# Mach_dieu_khien_tu_xa.net
KiCad netlist of a schematic drawn in Altium Designer
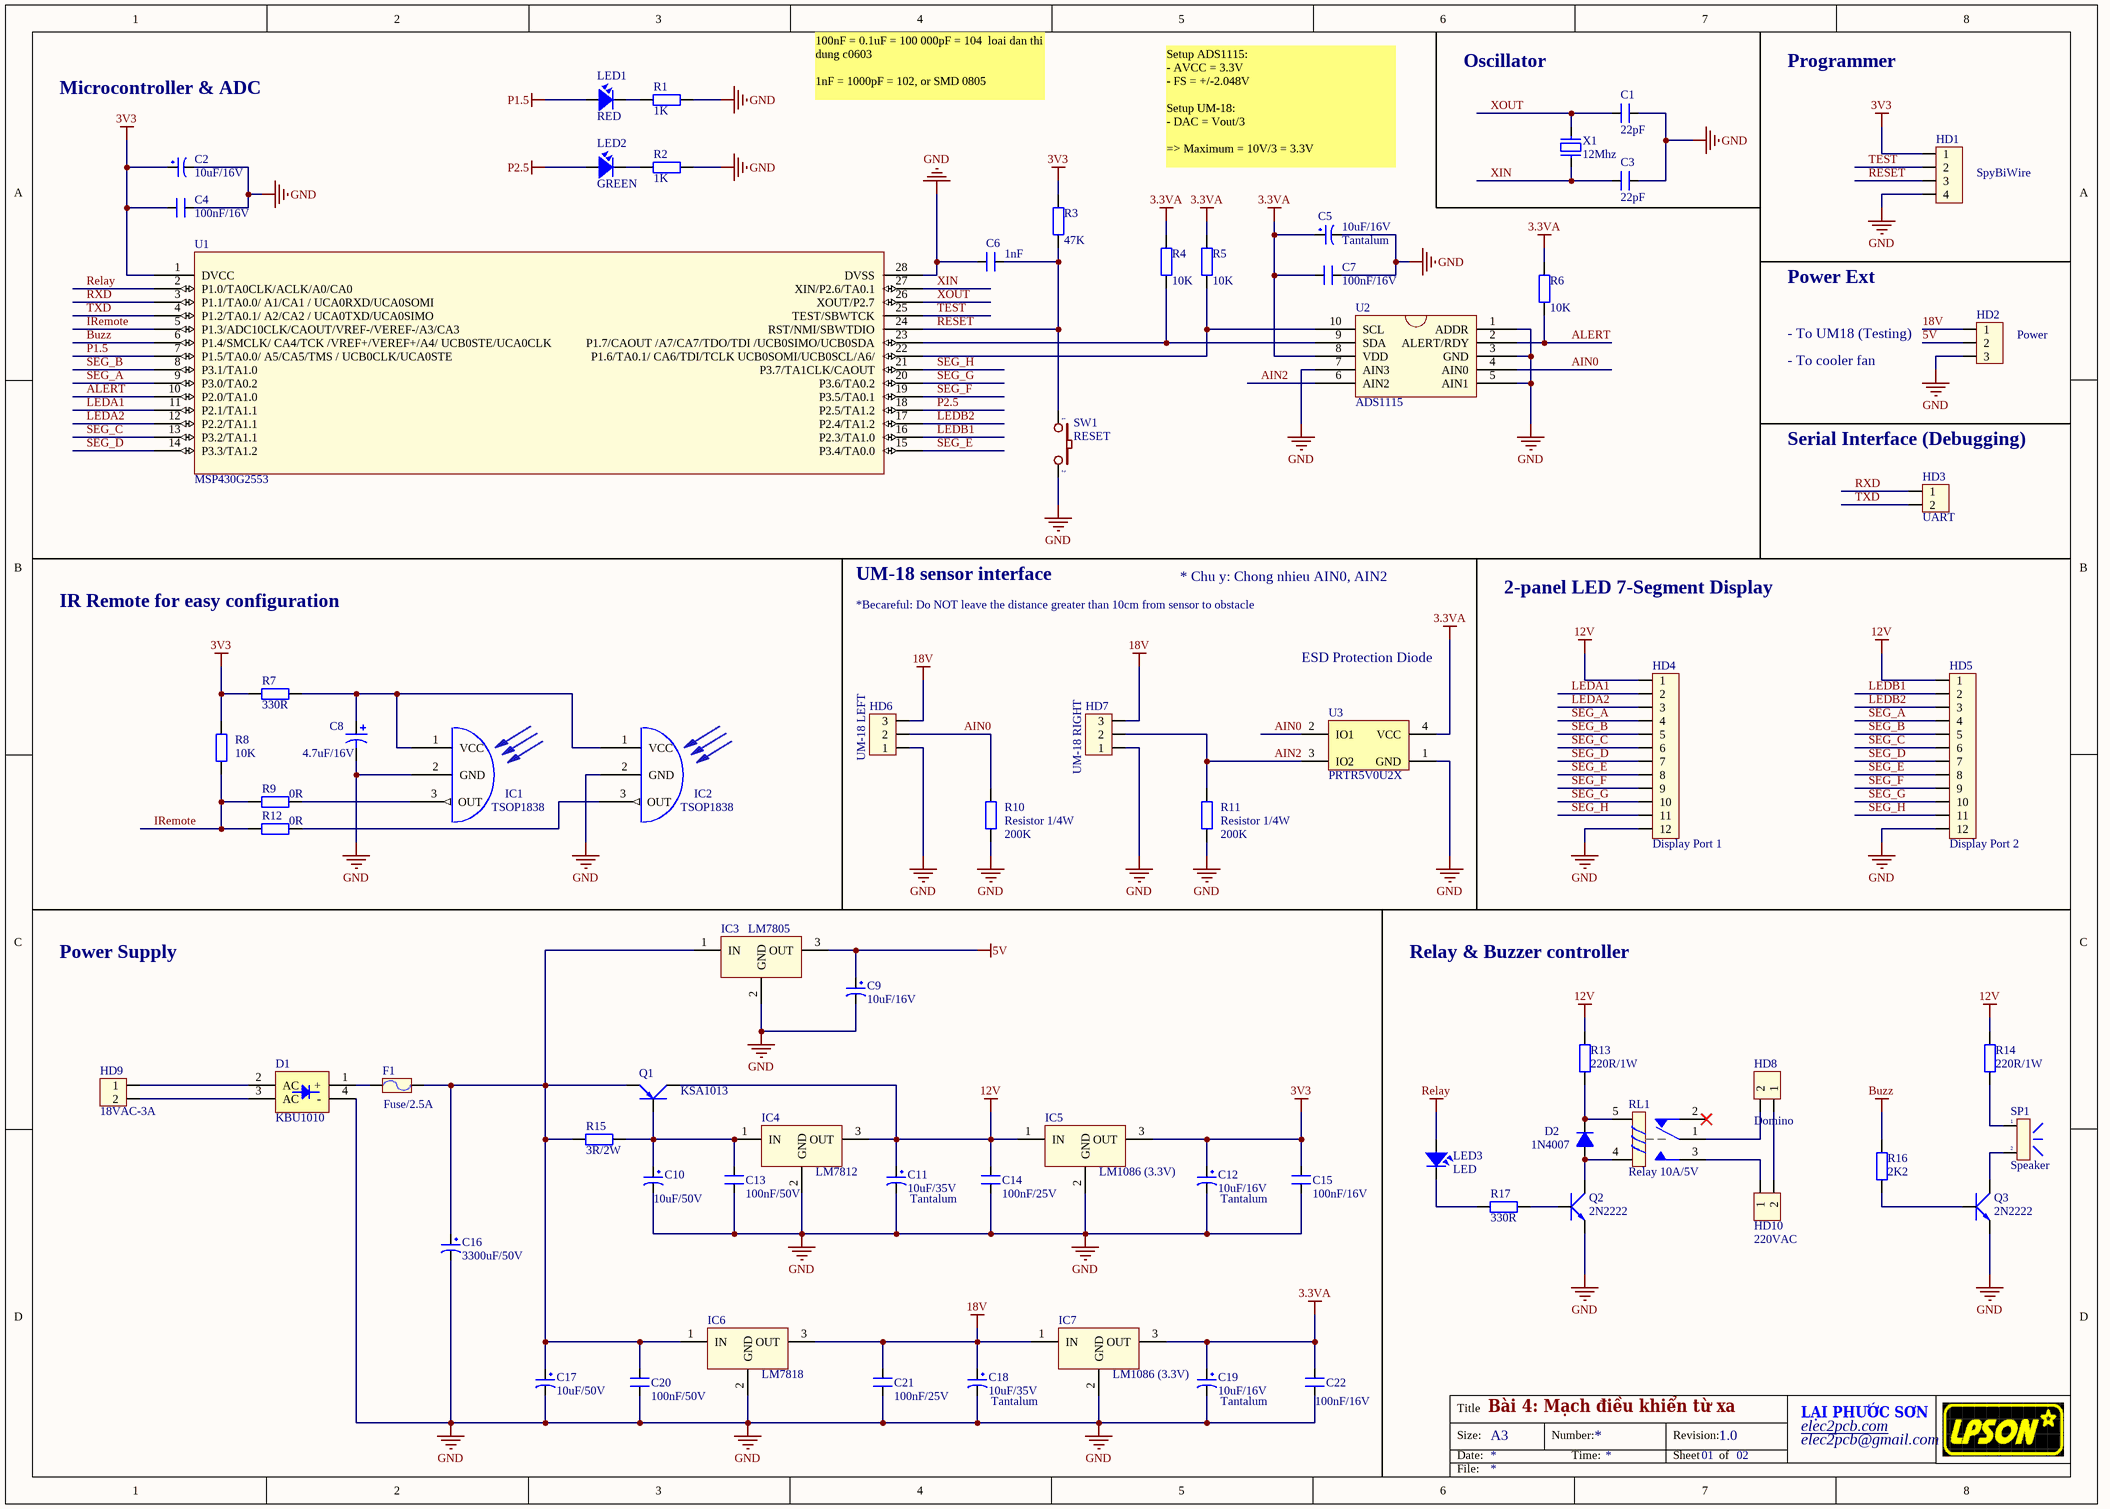
[diagram p0: Mach dieu khien tu xa.SchDoc]

(export (version "E")
  (design (tool "Eeschema 10.0.6"))
  (components
    (comp (ref "C1")
      (value "22pF")
      (footprint "C0603")
      (description "0805-SMD Capacitor")
      (libsource (lib "syhaunguyen") (part "CN1"))
    )
    (comp (ref "C2")
      (value "10uF/16V")
      (footprint "C0805")
      (description "Cap P  0,1uF < 22uF , 16 - 50V")
      (libsource (lib "") (part "CP1_1"))
    )
    (comp (ref "C3")
      (value "22pF")
      (footprint "C0603")
      (description "0805-SMD Capacitor")
      (libsource (lib "syhaunguyen") (part "CN1"))
    )
    (comp (ref "C4")
      (value "100nF/16V")
      (footprint "Tu gom 104")
      (description "Cap np 104 => 105pF")
      (libsource (lib "VNELEK") (part "CN2"))
    )
    (comp (ref "C5")
      (value "10uF/16V")
      (footprint "CAP_TANTA_10UF_16V")
      (description "Tantalum Capacitor")
      (fields (field (name "TYPE") "Tantalum"))
      (libsource (lib "") (part "CP1_1"))
    )
    (comp (ref "C6")
      (value "1nF")
      (footprint "C0805")
      (description "Cap np 104 => 105pF")
      (libsource (lib "VNELEK") (part "CN2"))
    )
    (comp (ref "C7")
      (value "100nF/16V")
      (footprint "Tu gom 104")
      (description "Cap np 104 => 105pF")
      (libsource (lib "VNELEK") (part "CN2"))
    )
    (comp (ref "C8")
      (value "4.7uF/16V")
      (footprint "C0805")
      (description "Polarized Capacitor (Radial)")
      (fields (field (name "Comment") "Cap Pol1") (field (name "PUBLISHER") "Altium Limited"))
      (libsource (lib "Miscellaneous Devices") (part "Cap Pol1"))
    )
    (comp (ref "C9")
      (value "10uF/16V")
      (footprint "CAP_10UF_16V")
      (description "Aluminium Capacitor")
      (libsource (lib "VNELEK") (part "CP1"))
    )
    (comp (ref "C10")
      (value "10uF/50V")
      (footprint "C_FC_10UF_50V")
      (description "Aluminium Capacitor")
      (libsource (lib "VNELEK") (part "CP1"))
    )
    (comp (ref "C11")
      (value "10uF/35V")
      (footprint "CAP_TANTA_10UF_35V")
      (description "Tantalum Capacitor")
      (fields (field (name "TYPE") "Tantalum"))
      (libsource (lib "VNELEK") (part "CP1"))
    )
    (comp (ref "C12")
      (value "10uF/16V")
      (footprint "CAP_TANTA_10UF_16V")
      (description "Tantalum Capacitor")
      (fields (field (name "TYPE") "Tantalum"))
      (libsource (lib "VNELEK") (part "CP1"))
    )
    (comp (ref "C13")
      (value "100nF/50V")
      (footprint "Tu gom 104")
      (description "Cap np 104 => 105pF")
      (libsource (lib "VNELEK") (part "CN2"))
    )
    (comp (ref "C14")
      (value "100nF/25V")
      (footprint "Tu gom 104")
      (description "Cap np 104 => 105pF")
      (libsource (lib "VNELEK") (part "CN2"))
    )
    (comp (ref "C15")
      (value "100nF/16V")
      (footprint "Tu gom 104")
      (description "Cap np 104 => 105pF")
      (libsource (lib "VNELEK") (part "CN2"))
    )
    (comp (ref "C16")
      (value "3300uF/50V")
      (footprint "CAP_3300UF_50V")
      (description "Cap P  0,1uF < 22uF , 16 - 50V")
      (libsource (lib "VNELEK") (part "CP1"))
    )
    (comp (ref "C17")
      (value "10uF/50V")
      (footprint "C_FC_10UF_50V")
      (description "Aluminium Capacitor")
      (libsource (lib "VNELEK") (part "CP1"))
    )
    (comp (ref "C18")
      (value "10uF/35V")
      (footprint "CAP_TANTA_10UF_35V")
      (description "Tantalum Capacitor")
      (fields (field (name "TYPE") "Tantalum"))
      (libsource (lib "VNELEK") (part "CP1"))
    )
    (comp (ref "C19")
      (value "10uF/16V")
      (footprint "CAP_TANTA_10UF_16V")
      (description "Tantalum Capacitor")
      (fields (field (name "TYPE") "Tantalum"))
      (libsource (lib "VNELEK") (part "CP1"))
    )
    (comp (ref "C20")
      (value "100nF/50V")
      (footprint "Tu gom 104")
      (description "Cap np 104 => 105pF")
      (libsource (lib "VNELEK") (part "CN2"))
    )
    (comp (ref "C21")
      (value "100nF/25V")
      (footprint "Tu gom 104")
      (description "Cap np 104 => 105pF")
      (libsource (lib "VNELEK") (part "CN2"))
    )
    (comp (ref "C22")
      (value "100nF/16V")
      (footprint "Tu gom 104")
      (description "Cap np 104 => 105pF")
      (libsource (lib "VNELEK") (part "CN2"))
    )
    (comp (ref "D1")
      (value "KBU1010")
      (footprint "KBU1010G")
      (description "10A glass passivated bridge rectifier")
      (libsource (lib "Tran Tuan") (part "KBU1010"))
    )
    (comp (ref "D2")
      (value "1N4007")
      (footprint "1N4007")
      (description "Diode 1A")
      (libsource (lib "VNELEK") (part "D1A"))
    )
    (comp (ref "F1")
      (value "Fuse/2.5A")
      (footprint "FUSE2_5A")
      (description "Fuse")
      (fields (field (name "DESIGNED BY") "VanDungEvn"))
      (libsource (lib "VNELEK") (part "Fuse"))
    )
    (comp (ref "HD1")
      (value "SpyBiWire")
      (footprint "Header_4")
      (description "Header 4 (Green)")
      (libsource (lib "VNELEK") (part "Hed4"))
    )
    (comp (ref "HD2")
      (value "Power")
      (footprint "CON3")
      (description "Header 3 (Green)")
      (libsource (lib "VNELEK") (part "Hed3"))
    )
    (comp (ref "HD3")
      (value "UART")
      (footprint "Header_2")
      (description "Header 2 (Green)")
      (libsource (lib "VNELEK") (part "Hed2"))
    )
    (comp (ref "HD4")
      (value "Display Port 1")
      (footprint "CON12")
      (description "Header 12")
      (libsource (lib "Tran Tuan") (part "Hed12"))
    )
    (comp (ref "HD5")
      (value "Display Port 2")
      (footprint "CON12")
      (description "Header 12")
      (libsource (lib "Tran Tuan") (part "Hed12"))
    )
    (comp (ref "HD6")
      (value "UM-18 LEFT")
      (footprint "CON3")
      (description "Header 3 (Green)")
      (libsource (lib "") (part "Hed3_1"))
    )
    (comp (ref "HD7")
      (value "UM-18 RIGHT")
      (footprint "CON3")
      (description "Header 3 (Green)")
      (libsource (lib "") (part "Hed3_1"))
    )
    (comp (ref "HD8")
      (value "Domino")
      (footprint "DOMINO2_GREEN")
      (description "Header 2 (Green)")
      (libsource (lib "VNELEK") (part "Hed2"))
    )
    (comp (ref "HD9")
      (value "18VAC-3A")
      (footprint "DOMINO2_GREEN")
      (description "Header 2 (Green)")
      (libsource (lib "") (part "Hed2_1"))
    )
    (comp (ref "HD10")
      (value "220VAC")
      (footprint "DOMINO2_GREEN")
      (description "Header 2 (Green)")
      (libsource (lib "") (part "Hed2_2"))
    )
    (comp (ref "IC1")
      (value "TSOP1838")
      (footprint "TSOP1838")
      (libsource (lib "Tran Tuan") (part "TSOP1838"))
    )
    (comp (ref "IC2")
      (value "TSOP1838")
      (footprint "TSOP1838")
      (libsource (lib "Tran Tuan") (part "TSOP1838"))
    )
    (comp (ref "IC3")
      (value "LM7805")
      (footprint "LM7805")
      (description "Linear Regulator")
      (libsource (lib "VNELEK") (part "LM78xx"))
    )
    (comp (ref "IC4")
      (value "LM7812")
      (footprint "LM7805")
      (description "Linear Regulator")
      (fields (field (name "MANUFACTURER") "Fairchild Semiconductor"))
      (libsource (lib "VNELEK") (part "LM78xx"))
    )
    (comp (ref "IC5")
      (value "LM1086 (3.3V)")
      (footprint "LM1086")
      (description "Linear Regulator")
      (libsource (lib "VNELEK") (part "LM78xx"))
    )
    (comp (ref "IC6")
      (value "LM7818")
      (footprint "LM7805")
      (description "Linear Regulator")
      (libsource (lib "VNELEK") (part "LM78xx"))
    )
    (comp (ref "IC7")
      (value "LM1086 (3.3V)")
      (footprint "LM1086")
      (description "Linear Regulator")
      (libsource (lib "VNELEK") (part "LM78xx"))
    )
    (comp (ref "LED1")
      (value "RED")
      (footprint "LED3R")
      (description "LED Single colour Green and Red")
      (libsource (lib "VNELEK") (part "LED"))
    )
    (comp (ref "LED2")
      (value "GREEN")
      (footprint "LED3R")
      (description "LED Single colour Green and Red")
      (libsource (lib "VNELEK") (part "LED"))
    )
    (comp (ref "LED3")
      (value "LED")
      (footprint "LED3R")
      (description "LED Single colour Green and Red")
      (libsource (lib "VNELEK") (part "LED"))
    )
    (comp (ref "Q1")
      (value "KSA1013")
      (footprint "KSA1013")
      (description "PNP 600mW, ECB")
      (fields (field (name "MANUFACTURER") "Fairchild Semiconductor"))
      (libsource (lib "VNELEK") (part "A1015"))
    )
    (comp (ref "Q2")
      (value "2N2222")
      (footprint "2N2222")
      (description "TRANS GP SS NPN LP 40V TO92")
      (libsource (lib "VNELEK") (part "C1815"))
    )
    (comp (ref "Q3")
      (value "2N2222")
      (footprint "2N2222")
      (description "TRANS GP SS NPN LP 40V TO92")
      (libsource (lib "VNELEK") (part "C1815"))
    )
    (comp (ref "R1")
      (value "1K")
      (footprint "RESC2012(0805)")
      (description "Resistor")
      (fields (field (name "Comment") "Res2") (field (name "PUBLISHER") "Altium Limited"))
      (libsource (lib "") (part "Res2_2"))
    )
    (comp (ref "R2")
      (value "1K")
      (footprint "RESC2012(0805)")
      (description "Resistor")
      (fields (field (name "Comment") "Res2") (field (name "PUBLISHER") "Altium Limited"))
      (libsource (lib "") (part "Res2_2"))
    )
    (comp (ref "R3")
      (value "47K")
      (footprint "RESC2012(0805)")
      (description "Resistor")
      (fields (field (name "Comment") "Res2") (field (name "PUBLISHER") "Altium Limited"))
      (libsource (lib "Miscellaneous Devices") (part "Res2"))
    )
    (comp (ref "R4")
      (value "10K")
      (footprint "RESC2012(0805)")
      (description "Resistor")
      (fields (field (name "Comment") "Res2") (field (name "PUBLISHER") "Altium Limited"))
      (libsource (lib "Miscellaneous Devices") (part "Res2"))
    )
    (comp (ref "R5")
      (value "10K")
      (footprint "RESC2012(0805)")
      (description "Resistor")
      (fields (field (name "Comment") "Res2") (field (name "PUBLISHER") "Altium Limited"))
      (libsource (lib "Miscellaneous Devices") (part "Res2"))
    )
    (comp (ref "R6")
      (value "10K")
      (footprint "RESC2012(0805)")
      (description "Resistor")
      (fields (field (name "Comment") "Res2") (field (name "PUBLISHER") "Altium Limited"))
      (libsource (lib "Miscellaneous Devices") (part "Res2"))
    )
    (comp (ref "R7")
      (value "330R")
      (footprint "RESC2012(0805)")
      (description "Resistor")
      (fields (field (name "Comment") "Res2") (field (name "PUBLISHER") "Altium Limited"))
      (libsource (lib "") (part "Res2_2"))
    )
    (comp (ref "R8")
      (value "10K")
      (footprint "RESC2012(0805)")
      (description "Resistor")
      (fields (field (name "Comment") "Res2") (field (name "PUBLISHER") "Altium Limited"))
      (libsource (lib "Miscellaneous Devices") (part "Res2"))
    )
    (comp (ref "R9")
      (value "0R")
      (footprint "RESC2012(0805)")
      (description "Resistor")
      (fields (field (name "Comment") "Res2") (field (name "PUBLISHER") "Altium Limited"))
      (libsource (lib "") (part "Res2_2"))
    )
    (comp (ref "R10")
      (value "Resistor 1/4W")
      (footprint "RESC2012(0805)")
      (fields (field (name "ALTIUM_VALUE") "200K"))
      (libsource (lib "") (part "Res2_1"))
    )
    (comp (ref "R11")
      (value "Resistor 1/4W")
      (footprint "RESC2012(0805)")
      (fields (field (name "ALTIUM_VALUE") "200K"))
      (libsource (lib "") (part "Res2_1"))
    )
    (comp (ref "R12")
      (value "0R")
      (footprint "RESC2012(0805)")
      (description "Resistor")
      (fields (field (name "Comment") "Res2") (field (name "PUBLISHER") "Altium Limited"))
      (libsource (lib "") (part "Res2_2"))
    )
    (comp (ref "R13")
      (value "220R/1W")
      (footprint "CFR1WS")
      (description "Resistor")
      (fields (field (name "Comment") "Res2") (field (name "PUBLISHER") "Altium Limited"))
      (libsource (lib "") (part "Res2_1"))
    )
    (comp (ref "R14")
      (value "220R/1W")
      (footprint "CFR1WS")
      (description "Resistor")
      (fields (field (name "Comment") "Res2") (field (name "PUBLISHER") "Altium Limited"))
      (libsource (lib "") (part "Res2_1"))
    )
    (comp (ref "R15")
      (value "3R/2W")
      (footprint "R2WD")
      (description "Resistor")
      (fields (field (name "Comment") "Res2") (field (name "PUBLISHER") "Altium Limited"))
      (libsource (lib "") (part "Res2_2"))
    )
    (comp (ref "R16")
      (value "2K2")
      (footprint "RES 1/4W CFR25")
      (description "Resistor")
      (fields (field (name "Comment") "Res2") (field (name "PUBLISHER") "Altium Limited"))
      (libsource (lib "") (part "Res2_1"))
    )
    (comp (ref "R17")
      (value "330R")
      (footprint "RES 1/4W CFR25")
      (description "Resistor")
      (fields (field (name "Comment") "Res2") (field (name "PUBLISHER") "Altium Limited"))
      (libsource (lib "") (part "Res2_2"))
    )
    (comp (ref "RL1")
      (value "Relay 10A/5V")
      (footprint "RL_10A_5V")
      (description "Relay SPDT,10A - 12VDC 5 Pin")
      (libsource (lib "VNELEK") (part "Relay 1"))
    )
    (comp (ref "SP1")
      (value "Speaker")
      (footprint "SPEAKER")
      (description "Speaker Chip")
      (libsource (lib "VNELEK") (part "SPK"))
    )
    (comp (ref "SW1")
      (value "RESET")
      (footprint "BUTTON 2PIN TRON")
      (description "Switch button 2 pin")
      (libsource (lib "VNELEK") (part "SW2"))
    )
    (comp (ref "U1")
      (value "MSP430G2553")
      (footprint "MSP430G2253IPW28R")
      (description "MSP430G2553 (28 pins)")
      (libsource (lib "Tran Tuan") (part "MSP430G2553"))
    )
    (comp (ref "U2")
      (value "ADS1115")
      (footprint "ADS1115")
      (description "Analog to Digital Converter")
      (libsource (lib "Tran Tuan") (part "ADS1115"))
    )
    (comp (ref "U3")
      (value "PRTR5V0U2X")
      (footprint "PRTR5V0U2X")
      (description "ESD protection diode")
      (libsource (lib "Tran Tuan") (part "PRTR5V0U2X"))
    )
    (comp (ref "X1")
      (value "12Mhz")
      (footprint "CRYSTAL")
      (description "Crystal For all Crystal 2pin.")
      (libsource (lib "syhaunguyen") (part "XT2"))
    )
  )
  (nets
    (net (code "1") (name "/AIN0") (class "Default")
      (node (ref "HD6") (pin "2") (pinfunction "2_2") (pintype "passive"))
      (node (ref "R10") (pin "1") (pinfunction "1_1") (pintype "passive"))
      (node (ref "U2") (pin "4") (pinfunction "AIN0_4") (pintype "passive"))
      (node (ref "U3") (pin "2") (pinfunction "IO1_2") (pintype "passive"))
    )
    (net (code "2") (name "/AIN2") (class "Default")
      (node (ref "HD7") (pin "2") (pinfunction "2_2") (pintype "passive"))
      (node (ref "R11") (pin "1") (pinfunction "1_1") (pintype "passive"))
      (node (ref "U2") (pin "6") (pinfunction "AIN2_6") (pintype "passive"))
      (node (ref "U3") (pin "3") (pinfunction "IO2_3") (pintype "passive"))
    )
    (net (code "3") (name "/ALERT") (class "Default")
      (node (ref "R6") (pin "1") (pinfunction "1_1") (pintype "passive"))
      (node (ref "U1") (pin "10") (pinfunction "P2.0/TA1.0_10") (pintype "bidirectional"))
      (node (ref "U2") (pin "2") (pinfunction "ALERT/RDY_2") (pintype "passive"))
    )
    (net (code "4") (name "/IRemote") (class "Default")
      (node (ref "R12") (pin "2") (pinfunction "2_2") (pintype "passive"))
      (node (ref "R8") (pin "1") (pinfunction "1_1") (pintype "passive"))
      (node (ref "R9") (pin "2") (pinfunction "2_2") (pintype "passive"))
      (node (ref "U1") (pin "5") (pinfunction "P1.3/ADC10CLK/CAOUT/VREF-/VEREF-/A3/CA3_5") (pintype "bidirectional"))
    )
    (net (code "5") (name "/LEDA1") (class "Default")
      (node (ref "HD4") (pin "2") (pinfunction "2_2") (pintype "passive"))
      (node (ref "U1") (pin "11") (pinfunction "P2.1/TA1.1_11") (pintype "bidirectional"))
    )
    (net (code "6") (name "/LEDA2") (class "Default")
      (node (ref "HD4") (pin "3") (pinfunction "3_3") (pintype "passive"))
      (node (ref "U1") (pin "12") (pinfunction "P2.2/TA1.1_12") (pintype "bidirectional"))
    )
    (net (code "7") (name "/LEDB1") (class "Default")
      (node (ref "HD5") (pin "2") (pinfunction "2_2") (pintype "passive"))
      (node (ref "U1") (pin "16") (pinfunction "P2.3/TA1.0_16") (pintype "bidirectional"))
    )
    (net (code "8") (name "/LEDB2") (class "Default")
      (node (ref "HD5") (pin "3") (pinfunction "3_3") (pintype "passive"))
      (node (ref "U1") (pin "17") (pinfunction "P2.4/TA1.2_17") (pintype "bidirectional"))
    )
    (net (code "9") (name "/RESET") (class "Default")
      (node (ref "C6") (pin "2") (pinfunction "2_2") (pintype "passive"))
      (node (ref "HD1") (pin "3") (pinfunction "3_3") (pintype "passive"))
      (node (ref "R3") (pin "1") (pinfunction "1_1") (pintype "passive"))
      (node (ref "SW1") (pin "1") (pinfunction "1_1") (pintype "passive"))
      (node (ref "U1") (pin "24") (pinfunction "RST/NMI/SBWTDIO_24") (pintype "passive"))
    )
    (net (code "10") (name "/RXD") (class "Default")
      (node (ref "HD3") (pin "1") (pinfunction "1_1") (pintype "passive"))
      (node (ref "U1") (pin "3") (pinfunction "P1.1/TA0.0/_A1/CA1_/_UCA0RXD/UCA0SOMI_3") (pintype "bidirectional"))
    )
    (net (code "11") (name "/SEG_A") (class "Default")
      (node (ref "HD4") (pin "4") (pinfunction "4_4") (pintype "passive"))
      (node (ref "HD5") (pin "4") (pinfunction "4_4") (pintype "passive"))
      (node (ref "U1") (pin "9") (pinfunction "P3.0/TA0.2_9") (pintype "bidirectional"))
    )
    (net (code "12") (name "/SEG_B") (class "Default")
      (node (ref "HD4") (pin "5") (pinfunction "5_5") (pintype "passive"))
      (node (ref "HD5") (pin "5") (pinfunction "5_5") (pintype "passive"))
      (node (ref "U1") (pin "8") (pinfunction "P3.1/TA1.0_8") (pintype "bidirectional"))
    )
    (net (code "13") (name "/SEG_C") (class "Default")
      (node (ref "HD4") (pin "6") (pinfunction "6_6") (pintype "passive"))
      (node (ref "HD5") (pin "6") (pinfunction "6_6") (pintype "passive"))
      (node (ref "U1") (pin "13") (pinfunction "P3.2/TA1.1_13") (pintype "bidirectional"))
    )
    (net (code "14") (name "/SEG_D") (class "Default")
      (node (ref "HD4") (pin "7") (pinfunction "7_7") (pintype "passive"))
      (node (ref "HD5") (pin "7") (pinfunction "7_7") (pintype "passive"))
      (node (ref "U1") (pin "14") (pinfunction "P3.3/TA1.2_14") (pintype "bidirectional"))
    )
    (net (code "15") (name "/SEG_E") (class "Default")
      (node (ref "HD4") (pin "8") (pinfunction "8_8") (pintype "passive"))
      (node (ref "HD5") (pin "8") (pinfunction "8_8") (pintype "passive"))
      (node (ref "U1") (pin "15") (pinfunction "P3.4/TA0.0_15") (pintype "bidirectional"))
    )
    (net (code "16") (name "/SEG_F") (class "Default")
      (node (ref "HD4") (pin "9") (pinfunction "9_9") (pintype "passive"))
      (node (ref "HD5") (pin "9") (pinfunction "9_9") (pintype "passive"))
      (node (ref "U1") (pin "19") (pinfunction "P3.5/TA0.1_19") (pintype "bidirectional"))
    )
    (net (code "17") (name "/SEG_G") (class "Default")
      (node (ref "HD4") (pin "10") (pinfunction "10_10") (pintype "passive"))
      (node (ref "HD5") (pin "10") (pinfunction "10_10") (pintype "passive"))
      (node (ref "U1") (pin "20") (pinfunction "P3.6/TA0.2_20") (pintype "bidirectional"))
    )
    (net (code "18") (name "/SEG_H") (class "Default")
      (node (ref "HD4") (pin "11") (pinfunction "11_11") (pintype "passive"))
      (node (ref "HD5") (pin "11") (pinfunction "11_11") (pintype "passive"))
      (node (ref "U1") (pin "21") (pinfunction "P3.7/TA1CLK/CAOUT_21") (pintype "bidirectional"))
    )
    (net (code "19") (name "/TEST") (class "Default")
      (node (ref "HD1") (pin "2") (pinfunction "2_2") (pintype "passive"))
      (node (ref "U1") (pin "25") (pinfunction "TEST/SBWTCK_25") (pintype "passive"))
    )
    (net (code "20") (name "/TXD") (class "Default")
      (node (ref "HD3") (pin "2") (pinfunction "2_2") (pintype "passive"))
      (node (ref "U1") (pin "4") (pinfunction "P1.2/TA0.1/_A2/CA2_/_UCA0TXD/UCA0SIMO_4") (pintype "bidirectional"))
    )
    (net (code "21") (name "/XIN") (class "Default")
      (node (ref "C3") (pin "2") (pinfunction "2_2") (pintype "passive"))
      (node (ref "U1") (pin "27") (pinfunction "XIN/P2.6/TA0.1_27") (pintype "bidirectional"))
      (node (ref "X1") (pin "2") (pinfunction "2_2") (pintype "passive"))
    )
    (net (code "22") (name "/XOUT") (class "Default")
      (node (ref "C1") (pin "2") (pinfunction "2_2") (pintype "passive"))
      (node (ref "U1") (pin "26") (pinfunction "XOUT/P2.7_26") (pintype "bidirectional"))
      (node (ref "X1") (pin "1") (pinfunction "1_1") (pintype "passive"))
    )
    (net (code "23") (name "3.3VA") (class "Default")
      (node (ref "C19") (pin "1") (pinfunction "1_1") (pintype "passive"))
      (node (ref "C22") (pin "2") (pinfunction "2_2") (pintype "passive"))
      (node (ref "C5") (pin "1") (pinfunction "1_1") (pintype "passive"))
      (node (ref "C7") (pin "2") (pinfunction "2_2") (pintype "passive"))
      (node (ref "IC7") (pin "3") (pinfunction "OUT_3") (pintype "passive"))
      (node (ref "R4") (pin "2") (pinfunction "2_2") (pintype "passive"))
      (node (ref "R5") (pin "2") (pinfunction "2_2") (pintype "passive"))
      (node (ref "R6") (pin "2") (pinfunction "2_2") (pintype "passive"))
      (node (ref "U2") (pin "8") (pinfunction "VDD_8") (pintype "passive"))
      (node (ref "U3") (pin "4") (pinfunction "VCC_4") (pintype "passive"))
    )
    (net (code "24") (name "3V3") (class "Default")
      (node (ref "C12") (pin "1") (pinfunction "1_1") (pintype "passive"))
      (node (ref "C15") (pin "2") (pinfunction "2_2") (pintype "passive"))
      (node (ref "C2") (pin "1") (pinfunction "1_1") (pintype "passive"))
      (node (ref "C4") (pin "2") (pinfunction "2_2") (pintype "passive"))
      (node (ref "HD1") (pin "1") (pinfunction "1_1") (pintype "passive"))
      (node (ref "IC5") (pin "3") (pinfunction "OUT_3") (pintype "passive"))
      (node (ref "R3") (pin "2") (pinfunction "2_2") (pintype "passive"))
      (node (ref "R7") (pin "2") (pinfunction "2_2") (pintype "passive"))
      (node (ref "R8") (pin "2") (pinfunction "2_2") (pintype "passive"))
      (node (ref "U1") (pin "1") (pinfunction "DVCC_1") (pintype "power_in"))
    )
    (net (code "25") (name "5V") (class "Default")
      (node (ref "C9") (pin "1") (pinfunction "1_1") (pintype "passive"))
      (node (ref "HD2") (pin "2") (pinfunction "2_2") (pintype "passive"))
      (node (ref "IC3") (pin "3") (pinfunction "OUT_3") (pintype "passive"))
    )
    (net (code "26") (name "12V") (class "Default")
      (node (ref "C11") (pin "1") (pinfunction "1_1") (pintype "passive"))
      (node (ref "C14") (pin "2") (pinfunction "2_2") (pintype "passive"))
      (node (ref "HD4") (pin "1") (pinfunction "1_1") (pintype "passive"))
      (node (ref "HD5") (pin "1") (pinfunction "1_1") (pintype "passive"))
      (node (ref "IC4") (pin "3") (pinfunction "OUT_3") (pintype "passive"))
      (node (ref "IC5") (pin "1") (pinfunction "IN_1") (pintype "passive"))
      (node (ref "Q1") (pin "2") (pinfunction "C_2") (pintype "passive"))
      (node (ref "R13") (pin "1") (pinfunction "1_1") (pintype "passive"))
      (node (ref "R14") (pin "1") (pinfunction "1_1") (pintype "passive"))
    )
    (net (code "27") (name "18V") (class "Default")
      (node (ref "C18") (pin "1") (pinfunction "1_1") (pintype "passive"))
      (node (ref "C21") (pin "2") (pinfunction "2_2") (pintype "passive"))
      (node (ref "HD2") (pin "1") (pinfunction "1_1") (pintype "passive"))
      (node (ref "HD6") (pin "3") (pinfunction "3_3") (pintype "passive"))
      (node (ref "HD7") (pin "3") (pinfunction "3_3") (pintype "passive"))
      (node (ref "IC6") (pin "3") (pinfunction "OUT_3") (pintype "passive"))
      (node (ref "IC7") (pin "1") (pinfunction "IN_1") (pintype "passive"))
    )
    (net (code "28") (name "Buzz") (class "Default")
      (node (ref "R16") (pin "1") (pinfunction "1_1") (pintype "passive"))
      (node (ref "U1") (pin "6") (pinfunction "P1.4/SMCLK/_CA4/TCK_/VREF+/VEREF+/A4/_UCB0STE/UCA0CLK_6") (pintype "bidirectional"))
    )
    (net (code "29") (name "GND") (class "Default")
      (node (ref "C1") (pin "1") (pinfunction "1_1") (pintype "passive"))
      (node (ref "C10") (pin "2") (pinfunction "2_2") (pintype "passive"))
      (node (ref "C11") (pin "2") (pinfunction "2_2") (pintype "passive"))
      (node (ref "C12") (pin "2") (pinfunction "2_2") (pintype "passive"))
      (node (ref "C13") (pin "1") (pinfunction "1_1") (pintype "passive"))
      (node (ref "C14") (pin "1") (pinfunction "1_1") (pintype "passive"))
      (node (ref "C15") (pin "1") (pinfunction "1_1") (pintype "passive"))
      (node (ref "C16") (pin "2") (pinfunction "2_2") (pintype "passive"))
      (node (ref "C17") (pin "2") (pinfunction "2_2") (pintype "passive"))
      (node (ref "C18") (pin "2") (pinfunction "2_2") (pintype "passive"))
      (node (ref "C19") (pin "2") (pinfunction "2_2") (pintype "passive"))
      (node (ref "C2") (pin "2") (pinfunction "2_2") (pintype "passive"))
      (node (ref "C20") (pin "1") (pinfunction "1_1") (pintype "passive"))
      (node (ref "C21") (pin "1") (pinfunction "1_1") (pintype "passive"))
      (node (ref "C22") (pin "1") (pinfunction "1_1") (pintype "passive"))
      (node (ref "C3") (pin "1") (pinfunction "1_1") (pintype "passive"))
      (node (ref "C4") (pin "1") (pinfunction "1_1") (pintype "passive"))
      (node (ref "C5") (pin "2") (pinfunction "2_2") (pintype "passive"))
      (node (ref "C6") (pin "1") (pinfunction "1_1") (pintype "passive"))
      (node (ref "C7") (pin "1") (pinfunction "1_1") (pintype "passive"))
      (node (ref "C8") (pin "2") (pinfunction "2_2") (pintype "passive"))
      (node (ref "C9") (pin "2") (pinfunction "2_2") (pintype "passive"))
      (node (ref "D1") (pin "4") (pinfunction "-_4") (pintype "power_in"))
      (node (ref "HD1") (pin "4") (pinfunction "4_4") (pintype "passive"))
      (node (ref "HD2") (pin "3") (pinfunction "3_3") (pintype "passive"))
      (node (ref "HD4") (pin "12") (pinfunction "12_12") (pintype "passive"))
      (node (ref "HD5") (pin "12") (pinfunction "12_12") (pintype "passive"))
      (node (ref "HD6") (pin "1") (pinfunction "1_1") (pintype "passive"))
      (node (ref "HD7") (pin "1") (pinfunction "1_1") (pintype "passive"))
      (node (ref "IC1") (pin "2") (pinfunction "GND_2") (pintype "power_in"))
      (node (ref "IC2") (pin "2") (pinfunction "GND_2") (pintype "power_in"))
      (node (ref "IC3") (pin "2") (pinfunction "GND_2") (pintype "passive"))
      (node (ref "IC4") (pin "2") (pinfunction "GND_2") (pintype "passive"))
      (node (ref "IC5") (pin "2") (pinfunction "GND_2") (pintype "passive"))
      (node (ref "IC6") (pin "2") (pinfunction "GND_2") (pintype "passive"))
      (node (ref "IC7") (pin "2") (pinfunction "GND_2") (pintype "passive"))
      (node (ref "Q2") (pin "1") (pinfunction "E_1") (pintype "passive"))
      (node (ref "Q3") (pin "1") (pinfunction "E_1") (pintype "passive"))
      (node (ref "R1") (pin "1") (pinfunction "1_1") (pintype "passive"))
      (node (ref "R10") (pin "2") (pinfunction "2_2") (pintype "passive"))
      (node (ref "R11") (pin "2") (pinfunction "2_2") (pintype "passive"))
      (node (ref "R2") (pin "1") (pinfunction "1_1") (pintype "passive"))
      (node (ref "SW1") (pin "2") (pinfunction "2_2") (pintype "passive"))
      (node (ref "U1") (pin "28") (pinfunction "DVSS_28") (pintype "passive"))
      (node (ref "U2") (pin "1") (pinfunction "ADDR_1") (pintype "passive"))
      (node (ref "U2") (pin "3") (pinfunction "GND_3") (pintype "passive"))
      (node (ref "U2") (pin "5") (pinfunction "AIN1_5") (pintype "passive"))
      (node (ref "U2") (pin "7") (pinfunction "AIN3_7") (pintype "passive"))
      (node (ref "U3") (pin "1") (pinfunction "GND_1") (pintype "passive"))
    )
    (net (code "30") (name "Net-(D1-+)") (class "Default")
      (node (ref "D1") (pin "1") (pinfunction "+_1") (pintype "power_in"))
      (node (ref "F1") (pin "1") (pinfunction "1_1") (pintype "passive"))
    )
    (net (code "31") (name "Net-(D1-AC-Pad2)") (class "Default")
      (node (ref "D1") (pin "2") (pinfunction "AC_2") (pintype "power_in"))
      (node (ref "HD9") (pin "1") (pinfunction "1_1") (pintype "passive"))
    )
    (net (code "32") (name "Net-(D1-AC-Pad3)") (class "Default")
      (node (ref "D1") (pin "3") (pinfunction "AC_3") (pintype "power_in"))
      (node (ref "HD9") (pin "2") (pinfunction "2_2") (pintype "passive"))
    )
    (net (code "33") (name "Net-(D2-A)") (class "Default")
      (node (ref "D2") (pin "1") (pinfunction "A_1") (pintype "passive"))
      (node (ref "Q2") (pin "3") (pinfunction "C_3") (pintype "passive"))
      (node (ref "RL1") (pin "4") (pinfunction "4_4") (pintype "passive"))
    )
    (net (code "34") (name "Net-(D2-K)") (class "Default")
      (node (ref "D2") (pin "2") (pinfunction "K_2") (pintype "passive"))
      (node (ref "R13") (pin "2") (pinfunction "2_2") (pintype "passive"))
      (node (ref "RL1") (pin "5") (pinfunction "5_5") (pintype "passive"))
    )
    (net (code "35") (name "Net-(HD8-Pad2)") (class "Default")
      (node (ref "HD8") (pin "2") (pinfunction "2_2") (pintype "passive"))
      (node (ref "RL1") (pin "1") (pinfunction "1_1") (pintype "passive"))
    )
    (net (code "36") (name "Net-(HD10-Pad1)") (class "Default")
      (node (ref "HD10") (pin "1") (pinfunction "1_1") (pintype "passive"))
      (node (ref "RL1") (pin "3") (pinfunction "3_3") (pintype "passive"))
    )
    (net (code "37") (name "Net-(HD10-Pad2)") (class "Default")
      (node (ref "HD10") (pin "2") (pinfunction "2_2") (pintype "passive"))
      (node (ref "HD8") (pin "1") (pinfunction "1_1") (pintype "passive"))
    )
    (net (code "38") (name "Net-(IC1-OUT)") (class "Default")
      (node (ref "IC1") (pin "3") (pinfunction "OUT_3") (pintype "output"))
      (node (ref "R9") (pin "1") (pinfunction "1_1") (pintype "passive"))
    )
    (net (code "39") (name "Net-(IC1-VCC)") (class "Default")
      (node (ref "C8") (pin "1") (pinfunction "1_1") (pintype "passive"))
      (node (ref "IC1") (pin "1") (pinfunction "VCC_1") (pintype "power_in"))
      (node (ref "IC2") (pin "1") (pinfunction "VCC_1") (pintype "power_in"))
      (node (ref "R7") (pin "1") (pinfunction "1_1") (pintype "passive"))
    )
    (net (code "40") (name "Net-(IC2-OUT)") (class "Default")
      (node (ref "IC2") (pin "3") (pinfunction "OUT_3") (pintype "output"))
      (node (ref "R12") (pin "1") (pinfunction "1_1") (pintype "passive"))
    )
    (net (code "41") (name "Net-(IC3-IN)") (class "Default")
      (node (ref "C16") (pin "1") (pinfunction "1_1") (pintype "passive"))
      (node (ref "C17") (pin "1") (pinfunction "1_1") (pintype "passive"))
      (node (ref "C20") (pin "2") (pinfunction "2_2") (pintype "passive"))
      (node (ref "F1") (pin "2") (pinfunction "2_2") (pintype "passive"))
      (node (ref "IC3") (pin "1") (pinfunction "IN_1") (pintype "passive"))
      (node (ref "IC6") (pin "1") (pinfunction "IN_1") (pintype "passive"))
      (node (ref "Q1") (pin "1") (pinfunction "E_1") (pintype "passive"))
      (node (ref "R15") (pin "2") (pinfunction "2_2") (pintype "passive"))
    )
    (net (code "42") (name "Net-(IC4-IN)") (class "Default")
      (node (ref "C10") (pin "1") (pinfunction "1_1") (pintype "passive"))
      (node (ref "C13") (pin "2") (pinfunction "2_2") (pintype "passive"))
      (node (ref "IC4") (pin "1") (pinfunction "IN_1") (pintype "passive"))
      (node (ref "Q1") (pin "3") (pinfunction "B_3") (pintype "passive"))
      (node (ref "R15") (pin "1") (pinfunction "1_1") (pintype "passive"))
    )
    (net (code "43") (name "Net-(LED1-Pad2)") (class "Default")
      (node (ref "LED1") (pin "2") (pinfunction "2_2") (pintype "passive"))
      (node (ref "R1") (pin "2") (pinfunction "2_2") (pintype "passive"))
    )
    (net (code "44") (name "Net-(LED2-Pad2)") (class "Default")
      (node (ref "LED2") (pin "2") (pinfunction "2_2") (pintype "passive"))
      (node (ref "R2") (pin "2") (pinfunction "2_2") (pintype "passive"))
    )
    (net (code "45") (name "Net-(LED3-Pad2)") (class "Default")
      (node (ref "LED3") (pin "2") (pinfunction "2_2") (pintype "passive"))
      (node (ref "R17") (pin "2") (pinfunction "2_2") (pintype "passive"))
    )
    (net (code "46") (name "Net-(Q2-B)") (class "Default")
      (node (ref "Q2") (pin "2") (pinfunction "B_2") (pintype "passive"))
      (node (ref "R17") (pin "1") (pinfunction "1_1") (pintype "passive"))
    )
    (net (code "47") (name "Net-(Q3-B)") (class "Default")
      (node (ref "Q3") (pin "2") (pinfunction "B_2") (pintype "passive"))
      (node (ref "R16") (pin "2") (pinfunction "2_2") (pintype "passive"))
    )
    (net (code "48") (name "Net-(Q3-C)") (class "Default")
      (node (ref "Q3") (pin "3") (pinfunction "C_3") (pintype "passive"))
      (node (ref "SP1") (pin "2") (pinfunction "2_2") (pintype "passive"))
    )
    (net (code "49") (name "Net-(R14-Pad2)") (class "Default")
      (node (ref "R14") (pin "2") (pinfunction "2_2") (pintype "passive"))
      (node (ref "SP1") (pin "1") (pinfunction "1_1") (pintype "passive"))
    )
    (net (code "50") (name "Net-(U1-P1.6{slash}TA0.1{slash}_CA6{slash}TDI{slash}TCLK_UCB0SOMI{slash}UCB0SCL{slash}A6{slash})") (class "Default")
      (node (ref "R5") (pin "1") (pinfunction "1_1") (pintype "passive"))
      (node (ref "U1") (pin "22") (pinfunction "P1.6/TA0.1/_CA6/TDI/TCLK_UCB0SOMI/UCB0SCL/A6/_22") (pintype "bidirectional"))
      (node (ref "U2") (pin "10") (pinfunction "SCL_10") (pintype "passive"))
    )
    (net (code "51") (name "Net-(U1-P1.7{slash}CAOUT_{slash}A7{slash}CA7{slash}TDO{slash}TDI_{slash}UCB0SIMO{slash}UCB0SDA)") (class "Default")
      (node (ref "R4") (pin "1") (pinfunction "1_1") (pintype "passive"))
      (node (ref "U1") (pin "23") (pinfunction "P1.7/CAOUT_/A7/CA7/TDO/TDI_/UCB0SIMO/UCB0SDA_23") (pintype "bidirectional"))
      (node (ref "U2") (pin "9") (pinfunction "SDA_9") (pintype "passive"))
    )
    (net (code "52") (name "P1.5") (class "Default")
      (node (ref "LED1") (pin "1") (pinfunction "1_1") (pintype "passive"))
      (node (ref "U1") (pin "7") (pinfunction "P1.5/TA0.0/_A5/CA5/TMS_/_UCB0CLK/UCA0STE_7") (pintype "bidirectional"))
    )
    (net (code "53") (name "P2.5") (class "Default")
      (node (ref "LED2") (pin "1") (pinfunction "1_1") (pintype "passive"))
      (node (ref "U1") (pin "18") (pinfunction "P2.5/TA1.2_18") (pintype "bidirectional"))
    )
    (net (code "54") (name "Relay") (class "Default")
      (node (ref "LED3") (pin "1") (pinfunction "1_1") (pintype "passive"))
      (node (ref "U1") (pin "2") (pinfunction "P1.0/TA0CLK/ACLK/A0/CA0_2") (pintype "bidirectional"))
    )
    (net (code "55") (name "unconnected-(RL1-Pad2)") (class "Default")
      (node (ref "RL1") (pin "2") (pinfunction "2_2") (pintype "passive+no_connect"))
    )
  )
)
